# final-project.net
KiCad netlist of a schematic drawn in Altium Designer
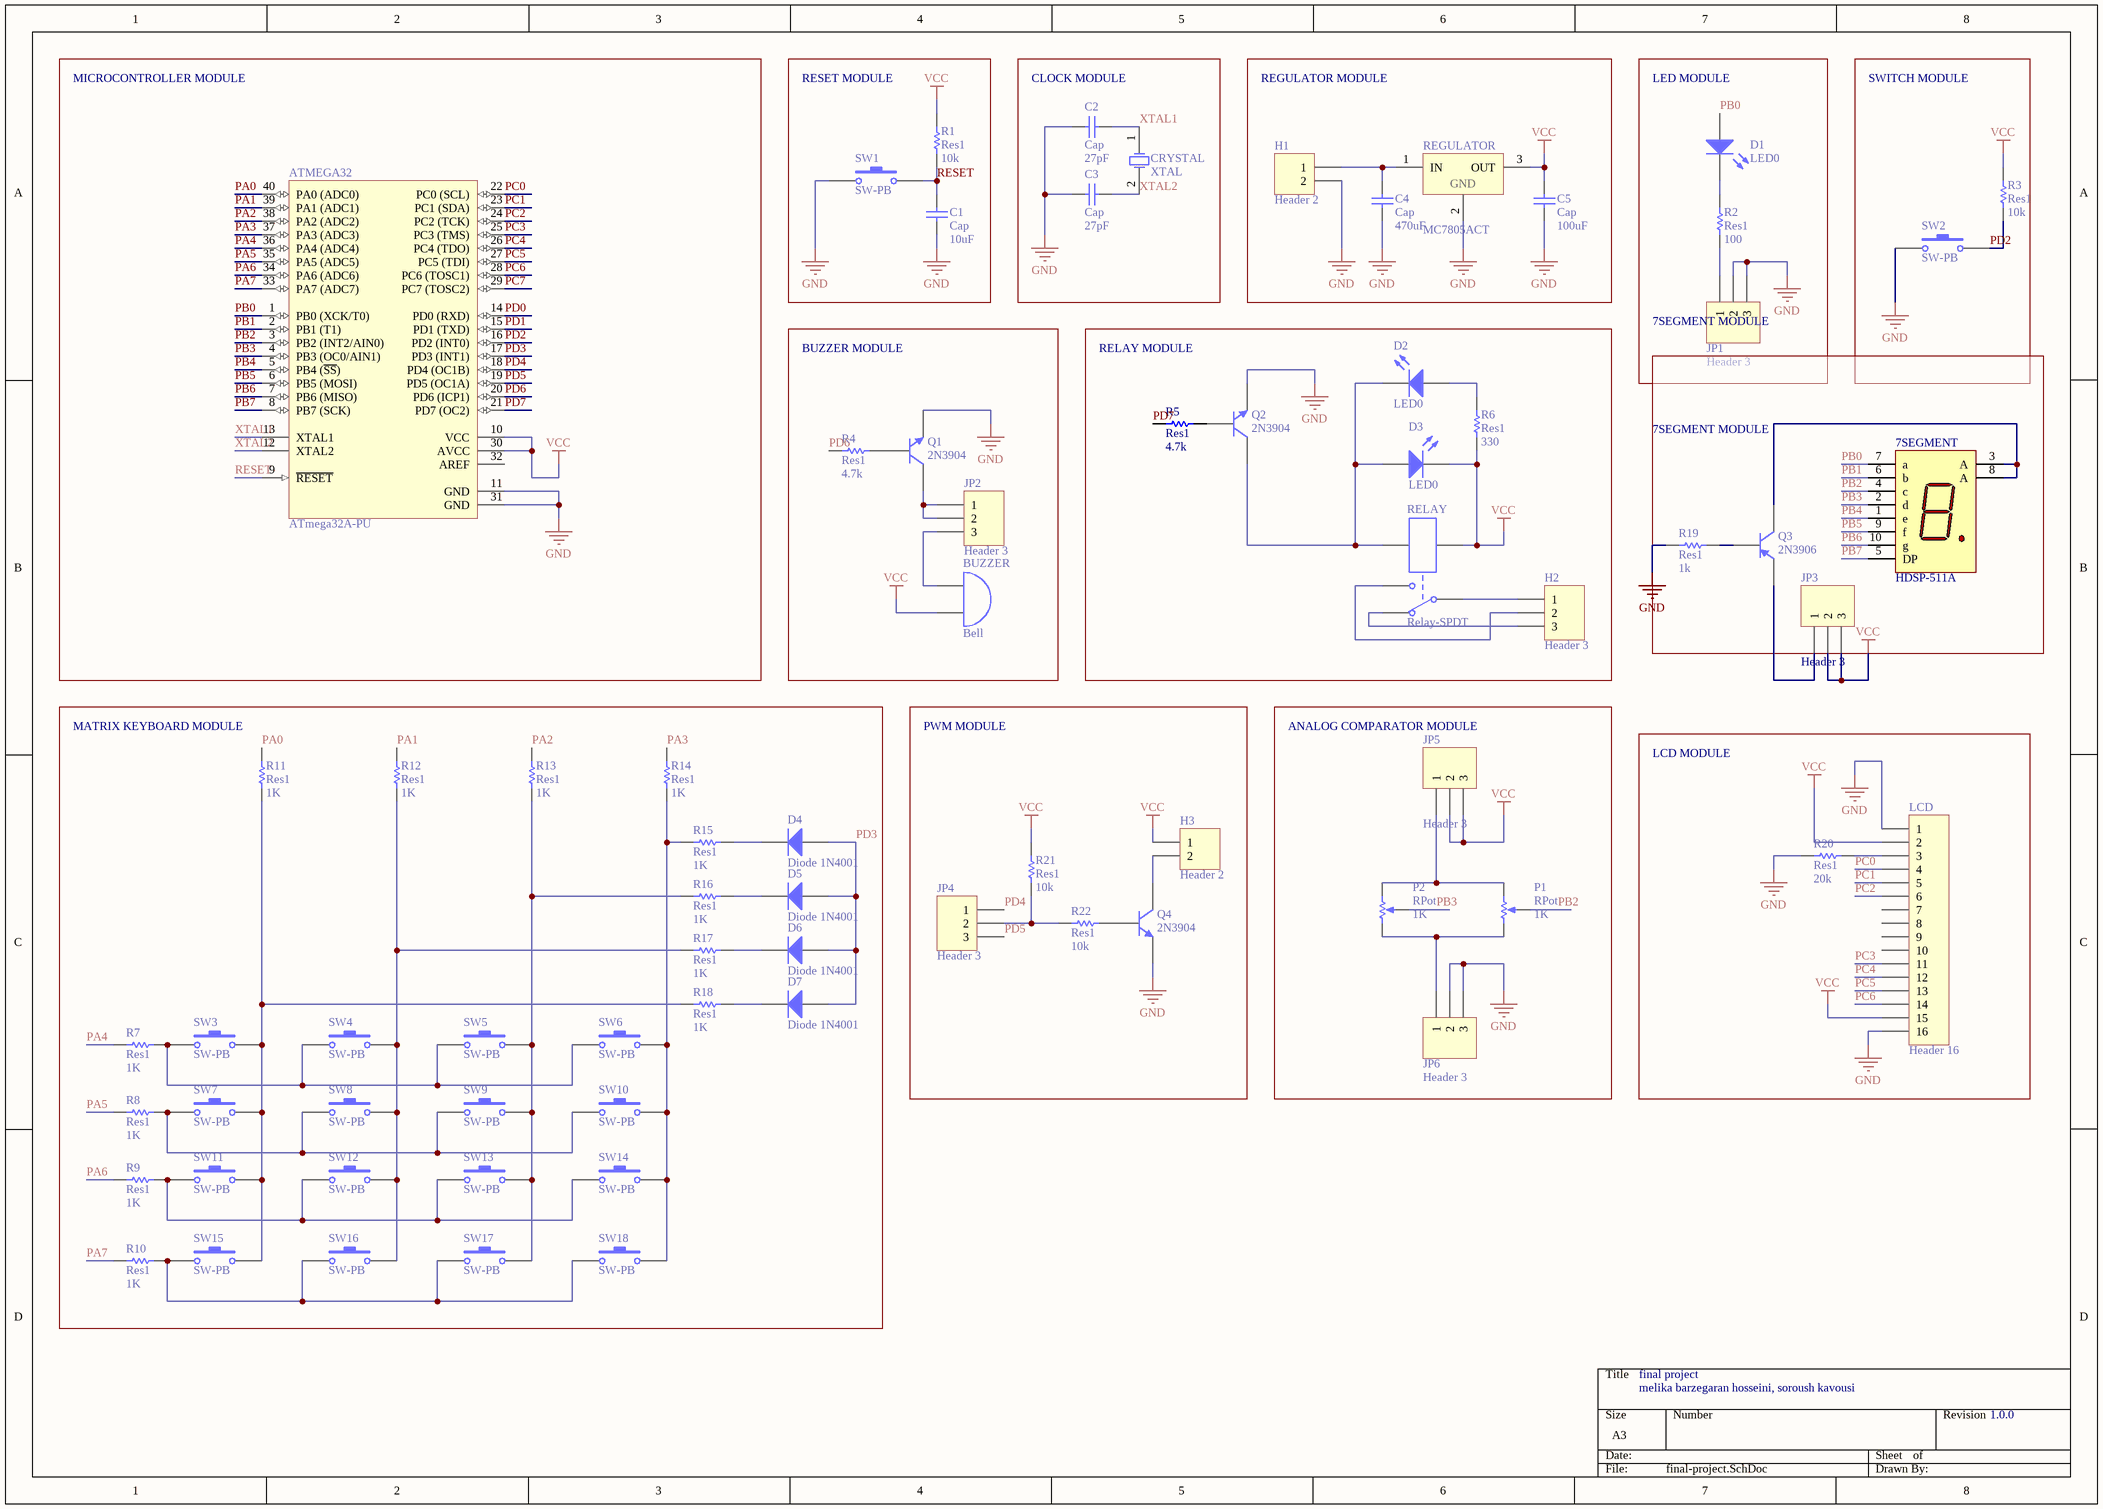
[diagram p0: final-project.SchDoc]

(export (version "E")
  (design (tool "Eeschema 10.0.6"))
  (components
    (comp (ref "7SEGMENT")
      (value "HDSP-511A")
      (footprint "HDSP-51")
      (description "14.22 mm General Purpose AlGaAs Red 7-Segment Display: CA, RH DP")
      (fields (field (name "PUBLISHER") "Altium Limited"))
      (libsource (lib "Agilent LED Display 7-Segment, 1-Digit") (part "HDSP-511A"))
    )
    (comp (ref "ATMEGA32")
      (value "ATmega32A-PU")
      (footprint "40P6")
      (fields (field (name "PUBLISHER") "Altium Limited"))
      (libsource (lib "Atmel Microcontroller 8-Bit megaAVR") (part "ATmega32A-PU"))
    )
    (comp (ref "BUZZER")
      (value "Bell")
      (footprint "PIN2")
      (description "Electrical Bell")
      (fields (field (name "PUBLISHER") "Altium Limited"))
      (libsource (lib "Miscellaneous Devices") (part "Bell"))
    )
    (comp (ref "C1")
      (value "Cap")
      (footprint "RAD-0.3")
      (description "Capacitor")
      (fields (field (name "ALTIUM_VALUE") "10uF") (field (name "PUBLISHER") "Altium Limited"))
      (libsource (lib "Miscellaneous Devices") (part "Cap"))
    )
    (comp (ref "C2")
      (value "Cap")
      (footprint "RAD-0.3")
      (description "Capacitor")
      (fields (field (name "ALTIUM_VALUE") "27pF") (field (name "PUBLISHER") "Altium Limited"))
      (libsource (lib "Miscellaneous Devices") (part "Cap"))
    )
    (comp (ref "C3")
      (value "Cap")
      (footprint "RAD-0.3")
      (description "Capacitor")
      (fields (field (name "ALTIUM_VALUE") "27pF") (field (name "PUBLISHER") "Altium Limited"))
      (libsource (lib "Miscellaneous Devices") (part "Cap"))
    )
    (comp (ref "C4")
      (value "Cap")
      (footprint "RAD-0.3")
      (description "Capacitor")
      (fields (field (name "ALTIUM_VALUE") "470uF") (field (name "PUBLISHER") "Altium Limited"))
      (libsource (lib "Miscellaneous Devices") (part "Cap"))
    )
    (comp (ref "C5")
      (value "Cap")
      (footprint "RAD-0.3")
      (description "Capacitor")
      (fields (field (name "ALTIUM_VALUE") "100uF") (field (name "PUBLISHER") "Altium Limited"))
      (libsource (lib "Miscellaneous Devices") (part "Cap"))
    )
    (comp (ref "CRYSTAL")
      (value "XTAL")
      (footprint "BCY-W2/D3.1")
      (description "Crystal Oscillator")
      (fields (field (name "PUBLISHER") "Altium Limited"))
      (libsource (lib "Miscellaneous Devices") (part "XTAL"))
    )
    (comp (ref "D1")
      (value "LED0")
      (footprint "RB5-10.5")
      (description "Typical INFRARED GaAs LED")
      (fields (field (name "PUBLISHER") "Altium Limited"))
      (libsource (lib "Miscellaneous Devices") (part "LED0"))
    )
    (comp (ref "D2")
      (value "LED0")
      (footprint "RB5-10.5")
      (description "Typical INFRARED GaAs LED")
      (fields (field (name "PUBLISHER") "Altium Limited"))
      (libsource (lib "Miscellaneous Devices") (part "LED0"))
    )
    (comp (ref "D3")
      (value "LED0")
      (footprint "RB5-10.5")
      (description "Typical INFRARED GaAs LED")
      (fields (field (name "PUBLISHER") "Altium Limited"))
      (libsource (lib "Miscellaneous Devices") (part "LED0"))
    )
    (comp (ref "D4")
      (value "Diode 1N4001")
      (footprint "DIO10.46-5.3x2.8")
      (description "1 Amp General Purpose Rectifier")
      (fields (field (name "PUBLISHER") "Altium Limited"))
      (libsource (lib "Miscellaneous Devices") (part "Diode 1N4001"))
    )
    (comp (ref "D5")
      (value "Diode 1N4001")
      (footprint "DIO10.46-5.3x2.8")
      (description "1 Amp General Purpose Rectifier")
      (fields (field (name "PUBLISHER") "Altium Limited"))
      (libsource (lib "Miscellaneous Devices") (part "Diode 1N4001"))
    )
    (comp (ref "D6")
      (value "Diode 1N4001")
      (footprint "DIO10.46-5.3x2.8")
      (description "1 Amp General Purpose Rectifier")
      (fields (field (name "PUBLISHER") "Altium Limited"))
      (libsource (lib "Miscellaneous Devices") (part "Diode 1N4001"))
    )
    (comp (ref "D7")
      (value "Diode 1N4001")
      (footprint "DIO10.46-5.3x2.8")
      (description "1 Amp General Purpose Rectifier")
      (fields (field (name "PUBLISHER") "Altium Limited"))
      (libsource (lib "Miscellaneous Devices") (part "Diode 1N4001"))
    )
    (comp (ref "H1")
      (value "Header 2")
      (footprint "HDR1X2")
      (description "Header, 2-Pin")
      (fields (field (name "PUBLISHER") "Altium Limited"))
      (libsource (lib "Miscellaneous Connectors") (part "Header 2"))
    )
    (comp (ref "H2")
      (value "Header 3")
      (footprint "HDR1X3")
      (description "Header, 3-Pin")
      (fields (field (name "PUBLISHER") "Altium Limited"))
      (libsource (lib "") (part "Header 3_3"))
    )
    (comp (ref "H3")
      (value "Header 2")
      (footprint "HDR1X2")
      (description "Header, 2-Pin")
      (fields (field (name "PUBLISHER") "Altium Limited"))
      (libsource (lib "") (part "Header 2_1"))
    )
    (comp (ref "JP1")
      (value "Header 3")
      (footprint "HDR1X3")
      (description "Header, 3-Pin")
      (fields (field (name "PUBLISHER") "Altium Limited"))
      (libsource (lib "") (part "Header 3_1"))
    )
    (comp (ref "JP2")
      (value "Header 3")
      (footprint "HDR1X3")
      (description "Header, 3-Pin")
      (fields (field (name "PUBLISHER") "Altium Limited"))
      (libsource (lib "") (part "Header 3_3"))
    )
    (comp (ref "JP3")
      (value "Header 3")
      (footprint "HDR1X3")
      (description "Header, 3-Pin")
      (fields (field (name "PUBLISHER") "Altium Limited"))
      (libsource (lib "Miscellaneous Connectors") (part "Header 3"))
    )
    (comp (ref "JP4")
      (value "Header 3")
      (footprint "HDR1X3")
      (description "Header, 3-Pin")
      (fields (field (name "PUBLISHER") "Altium Limited"))
      (libsource (lib "") (part "Header 3_2"))
    )
    (comp (ref "JP5")
      (value "Header 3")
      (footprint "HDR1X3")
      (description "Header, 3-Pin")
      (fields (field (name "PUBLISHER") "Altium Limited"))
      (libsource (lib "Miscellaneous Connectors") (part "Header 3"))
    )
    (comp (ref "JP6")
      (value "Header 3")
      (footprint "HDR1X3")
      (description "Header, 3-Pin")
      (fields (field (name "PUBLISHER") "Altium Limited"))
      (libsource (lib "") (part "Header 3_1"))
    )
    (comp (ref "LCD")
      (value "Header 16")
      (footprint "HDR1X16")
      (description "Header, 16-Pin")
      (fields (field (name "PUBLISHER") "Altium Limited"))
      (libsource (lib "Miscellaneous Connectors") (part "Header 16"))
    )
    (comp (ref "P1")
      (value "RPot")
      (footprint "VR5")
      (description "Potentiometer")
      (fields (field (name "ALTIUM_VALUE") "1K") (field (name "PUBLISHER") "Altium Limited"))
      (libsource (lib "Miscellaneous Devices") (part "RPot"))
    )
    (comp (ref "P2")
      (value "RPot")
      (footprint "VR5")
      (description "Potentiometer")
      (fields (field (name "ALTIUM_VALUE") "1K") (field (name "PUBLISHER") "Altium Limited"))
      (libsource (lib "Miscellaneous Devices") (part "RPot"))
    )
    (comp (ref "Q1")
      (value "2N3904")
      (footprint "HDR1X3")
      (description "NPN General Purpose Amplifier")
      (fields (field (name "PUBLISHER") "Altium Limited"))
      (libsource (lib "Miscellaneous Devices") (part "2N3904"))
    )
    (comp (ref "Q2")
      (value "2N3904")
      (footprint "HDR1X3")
      (description "NPN General Purpose Amplifier")
      (fields (field (name "PUBLISHER") "Altium Limited"))
      (libsource (lib "Miscellaneous Devices") (part "2N3904"))
    )
    (comp (ref "Q3")
      (value "2N3906")
      (footprint "HDR1X3")
      (description "PNP General Purpose Amplifier")
      (fields (field (name "PUBLISHER") "Altium Limited"))
      (libsource (lib "Miscellaneous Devices") (part "2N3906"))
    )
    (comp (ref "Q4")
      (value "2N3904")
      (footprint "HDR1X3")
      (description "NPN General Purpose Amplifier")
      (fields (field (name "PUBLISHER") "Altium Limited"))
      (libsource (lib "Miscellaneous Devices") (part "2N3904"))
    )
    (comp (ref "R1")
      (value "Res1")
      (footprint "AXIAL-0.3")
      (description "Resistor")
      (fields (field (name "ALTIUM_VALUE") "10k") (field (name "PUBLISHER") "Altium Limited"))
      (libsource (lib "Miscellaneous Devices") (part "Res1"))
    )
    (comp (ref "R2")
      (value "Res1")
      (footprint "AXIAL-0.3")
      (description "Resistor")
      (fields (field (name "ALTIUM_VALUE") "100") (field (name "PUBLISHER") "Altium Limited"))
      (libsource (lib "Miscellaneous Devices") (part "Res1"))
    )
    (comp (ref "R3")
      (value "Res1")
      (footprint "AXIAL-0.3")
      (description "Resistor")
      (fields (field (name "ALTIUM_VALUE") "10k") (field (name "PUBLISHER") "Altium Limited"))
      (libsource (lib "Miscellaneous Devices") (part "Res1"))
    )
    (comp (ref "R4")
      (value "Res1")
      (footprint "AXIAL-0.3")
      (description "Resistor")
      (fields (field (name "ALTIUM_VALUE") "4.7k") (field (name "PUBLISHER") "Altium Limited"))
      (libsource (lib "Miscellaneous Devices") (part "Res1"))
    )
    (comp (ref "R5")
      (value "Res1")
      (footprint "AXIAL-0.3")
      (description "Resistor")
      (fields (field (name "ALTIUM_VALUE") "4.7k") (field (name "PUBLISHER") "Altium Limited"))
      (libsource (lib "Miscellaneous Devices") (part "Res1"))
    )
    (comp (ref "R6")
      (value "Res1")
      (footprint "AXIAL-0.3")
      (description "Resistor")
      (fields (field (name "ALTIUM_VALUE") "330") (field (name "PUBLISHER") "Altium Limited"))
      (libsource (lib "Miscellaneous Devices") (part "Res1"))
    )
    (comp (ref "R7")
      (value "Res1")
      (footprint "AXIAL-0.3")
      (description "Resistor")
      (fields (field (name "ALTIUM_VALUE") "1K") (field (name "PUBLISHER") "Altium Limited"))
      (libsource (lib "Miscellaneous Devices") (part "Res1"))
    )
    (comp (ref "R8")
      (value "Res1")
      (footprint "AXIAL-0.3")
      (description "Resistor")
      (fields (field (name "ALTIUM_VALUE") "1K") (field (name "PUBLISHER") "Altium Limited"))
      (libsource (lib "Miscellaneous Devices") (part "Res1"))
    )
    (comp (ref "R9")
      (value "Res1")
      (footprint "AXIAL-0.3")
      (description "Resistor")
      (fields (field (name "ALTIUM_VALUE") "1K") (field (name "PUBLISHER") "Altium Limited"))
      (libsource (lib "Miscellaneous Devices") (part "Res1"))
    )
    (comp (ref "R10")
      (value "Res1")
      (footprint "AXIAL-0.3")
      (description "Resistor")
      (fields (field (name "ALTIUM_VALUE") "1K") (field (name "PUBLISHER") "Altium Limited"))
      (libsource (lib "Miscellaneous Devices") (part "Res1"))
    )
    (comp (ref "R11")
      (value "Res1")
      (footprint "AXIAL-0.3")
      (description "Resistor")
      (fields (field (name "ALTIUM_VALUE") "1K") (field (name "PUBLISHER") "Altium Limited"))
      (libsource (lib "Miscellaneous Devices") (part "Res1"))
    )
    (comp (ref "R12")
      (value "Res1")
      (footprint "AXIAL-0.3")
      (description "Resistor")
      (fields (field (name "ALTIUM_VALUE") "1K") (field (name "PUBLISHER") "Altium Limited"))
      (libsource (lib "Miscellaneous Devices") (part "Res1"))
    )
    (comp (ref "R13")
      (value "Res1")
      (footprint "AXIAL-0.3")
      (description "Resistor")
      (fields (field (name "ALTIUM_VALUE") "1K") (field (name "PUBLISHER") "Altium Limited"))
      (libsource (lib "Miscellaneous Devices") (part "Res1"))
    )
    (comp (ref "R14")
      (value "Res1")
      (footprint "AXIAL-0.3")
      (description "Resistor")
      (fields (field (name "ALTIUM_VALUE") "1K") (field (name "PUBLISHER") "Altium Limited"))
      (libsource (lib "Miscellaneous Devices") (part "Res1"))
    )
    (comp (ref "R15")
      (value "Res1")
      (footprint "AXIAL-0.3")
      (description "Resistor")
      (fields (field (name "ALTIUM_VALUE") "1K") (field (name "PUBLISHER") "Altium Limited"))
      (libsource (lib "Miscellaneous Devices") (part "Res1"))
    )
    (comp (ref "R16")
      (value "Res1")
      (footprint "AXIAL-0.3")
      (description "Resistor")
      (fields (field (name "ALTIUM_VALUE") "1K") (field (name "PUBLISHER") "Altium Limited"))
      (libsource (lib "Miscellaneous Devices") (part "Res1"))
    )
    (comp (ref "R17")
      (value "Res1")
      (footprint "AXIAL-0.3")
      (description "Resistor")
      (fields (field (name "ALTIUM_VALUE") "1K") (field (name "PUBLISHER") "Altium Limited"))
      (libsource (lib "Miscellaneous Devices") (part "Res1"))
    )
    (comp (ref "R18")
      (value "Res1")
      (footprint "AXIAL-0.3")
      (description "Resistor")
      (fields (field (name "ALTIUM_VALUE") "1K") (field (name "PUBLISHER") "Altium Limited"))
      (libsource (lib "Miscellaneous Devices") (part "Res1"))
    )
    (comp (ref "R19")
      (value "Res1")
      (footprint "AXIAL-0.3")
      (description "Resistor")
      (fields (field (name "ALTIUM_VALUE") "1k") (field (name "PUBLISHER") "Altium Limited"))
      (libsource (lib "Miscellaneous Devices") (part "Res1"))
    )
    (comp (ref "R20")
      (value "Res1")
      (footprint "AXIAL-0.3")
      (description "Resistor")
      (fields (field (name "ALTIUM_VALUE") "20k") (field (name "PUBLISHER") "Altium Limited"))
      (libsource (lib "Miscellaneous Devices") (part "Res1"))
    )
    (comp (ref "R21")
      (value "Res1")
      (footprint "AXIAL-0.3")
      (description "Resistor")
      (fields (field (name "ALTIUM_VALUE") "10k") (field (name "PUBLISHER") "Altium Limited"))
      (libsource (lib "Miscellaneous Devices") (part "Res1"))
    )
    (comp (ref "R22")
      (value "Res1")
      (footprint "AXIAL-0.3")
      (description "Resistor")
      (fields (field (name "ALTIUM_VALUE") "10k") (field (name "PUBLISHER") "Altium Limited"))
      (libsource (lib "Miscellaneous Devices") (part "Res1"))
    )
    (comp (ref "REGULATOR")
      (value "MC7805ACT")
      (footprint "221A-04")
      (description "3-Terminal Positive Fixed Voltage Regulator")
      (fields (field (name "PUBLISHER") "Altium Limited"))
      (libsource (lib "Motorola Power Mgt Voltage Regulator") (part "MC7805ACT"))
    )
    (comp (ref "RELAY")
      (value "Relay-SPDT")
      (footprint "DIP-P5/X1.65")
      (description "Single-Pole Dual-Throw Relay")
      (fields (field (name "PUBLISHER") "Altium Limited"))
      (libsource (lib "Miscellaneous Devices") (part "Relay-SPDT"))
    )
    (comp (ref "SW1")
      (value "SW-PB")
      (footprint "SPST-2")
      (description "Switch")
      (fields (field (name "PUBLISHER") "Altium Limited"))
      (libsource (lib "Miscellaneous Devices") (part "SW-PB"))
    )
    (comp (ref "SW2")
      (value "SW-PB")
      (footprint "SPST-2")
      (description "Switch")
      (fields (field (name "PUBLISHER") "Altium Limited"))
      (libsource (lib "Miscellaneous Devices") (part "SW-PB"))
    )
    (comp (ref "SW3")
      (value "SW-PB")
      (footprint "SPST-2")
      (description "Switch")
      (fields (field (name "PUBLISHER") "Altium Limited"))
      (libsource (lib "Miscellaneous Devices") (part "SW-PB"))
    )
    (comp (ref "SW4")
      (value "SW-PB")
      (footprint "SPST-2")
      (description "Switch")
      (fields (field (name "PUBLISHER") "Altium Limited"))
      (libsource (lib "Miscellaneous Devices") (part "SW-PB"))
    )
    (comp (ref "SW5")
      (value "SW-PB")
      (footprint "SPST-2")
      (description "Switch")
      (fields (field (name "PUBLISHER") "Altium Limited"))
      (libsource (lib "Miscellaneous Devices") (part "SW-PB"))
    )
    (comp (ref "SW6")
      (value "SW-PB")
      (footprint "SPST-2")
      (description "Switch")
      (fields (field (name "PUBLISHER") "Altium Limited"))
      (libsource (lib "Miscellaneous Devices") (part "SW-PB"))
    )
    (comp (ref "SW7")
      (value "SW-PB")
      (footprint "SPST-2")
      (description "Switch")
      (fields (field (name "PUBLISHER") "Altium Limited"))
      (libsource (lib "Miscellaneous Devices") (part "SW-PB"))
    )
    (comp (ref "SW8")
      (value "SW-PB")
      (footprint "SPST-2")
      (description "Switch")
      (fields (field (name "PUBLISHER") "Altium Limited"))
      (libsource (lib "Miscellaneous Devices") (part "SW-PB"))
    )
    (comp (ref "SW9")
      (value "SW-PB")
      (footprint "SPST-2")
      (description "Switch")
      (fields (field (name "PUBLISHER") "Altium Limited"))
      (libsource (lib "Miscellaneous Devices") (part "SW-PB"))
    )
    (comp (ref "SW10")
      (value "SW-PB")
      (footprint "SPST-2")
      (description "Switch")
      (fields (field (name "PUBLISHER") "Altium Limited"))
      (libsource (lib "Miscellaneous Devices") (part "SW-PB"))
    )
    (comp (ref "SW11")
      (value "SW-PB")
      (footprint "SPST-2")
      (description "Switch")
      (fields (field (name "PUBLISHER") "Altium Limited"))
      (libsource (lib "Miscellaneous Devices") (part "SW-PB"))
    )
    (comp (ref "SW12")
      (value "SW-PB")
      (footprint "SPST-2")
      (description "Switch")
      (fields (field (name "PUBLISHER") "Altium Limited"))
      (libsource (lib "Miscellaneous Devices") (part "SW-PB"))
    )
    (comp (ref "SW13")
      (value "SW-PB")
      (footprint "SPST-2")
      (description "Switch")
      (fields (field (name "PUBLISHER") "Altium Limited"))
      (libsource (lib "Miscellaneous Devices") (part "SW-PB"))
    )
    (comp (ref "SW14")
      (value "SW-PB")
      (footprint "SPST-2")
      (description "Switch")
      (fields (field (name "PUBLISHER") "Altium Limited"))
      (libsource (lib "Miscellaneous Devices") (part "SW-PB"))
    )
    (comp (ref "SW15")
      (value "SW-PB")
      (footprint "SPST-2")
      (description "Switch")
      (fields (field (name "PUBLISHER") "Altium Limited"))
      (libsource (lib "Miscellaneous Devices") (part "SW-PB"))
    )
    (comp (ref "SW16")
      (value "SW-PB")
      (footprint "SPST-2")
      (description "Switch")
      (fields (field (name "PUBLISHER") "Altium Limited"))
      (libsource (lib "Miscellaneous Devices") (part "SW-PB"))
    )
    (comp (ref "SW17")
      (value "SW-PB")
      (footprint "SPST-2")
      (description "Switch")
      (fields (field (name "PUBLISHER") "Altium Limited"))
      (libsource (lib "Miscellaneous Devices") (part "SW-PB"))
    )
    (comp (ref "SW18")
      (value "SW-PB")
      (footprint "SPST-2")
      (description "Switch")
      (fields (field (name "PUBLISHER") "Altium Limited"))
      (libsource (lib "Miscellaneous Devices") (part "SW-PB"))
    )
  )
  (nets
    (net (code "1") (name "/PA0") (class "Default")
      (node (ref "ATMEGA32") (pin "40") (pinfunction "PA0_(ADC0)_40") (pintype "bidirectional"))
      (node (ref "R11") (pin "2") (pinfunction "2_2") (pintype "passive"))
    )
    (net (code "2") (name "/PA1") (class "Default")
      (node (ref "ATMEGA32") (pin "39") (pinfunction "PA1_(ADC1)_39") (pintype "bidirectional"))
      (node (ref "R12") (pin "2") (pinfunction "2_2") (pintype "passive"))
    )
    (net (code "3") (name "/PA2") (class "Default")
      (node (ref "ATMEGA32") (pin "38") (pinfunction "PA2_(ADC2)_38") (pintype "bidirectional"))
      (node (ref "R13") (pin "2") (pinfunction "2_2") (pintype "passive"))
    )
    (net (code "4") (name "/PA3") (class "Default")
      (node (ref "ATMEGA32") (pin "37") (pinfunction "PA3_(ADC3)_37") (pintype "bidirectional"))
      (node (ref "R14") (pin "2") (pinfunction "2_2") (pintype "passive"))
    )
    (net (code "5") (name "/PA4") (class "Default")
      (node (ref "ATMEGA32") (pin "36") (pinfunction "PA4_(ADC4)_36") (pintype "bidirectional"))
      (node (ref "R7") (pin "1") (pinfunction "1_1") (pintype "passive"))
    )
    (net (code "6") (name "/PA5") (class "Default")
      (node (ref "ATMEGA32") (pin "35") (pinfunction "PA5_(ADC5)_35") (pintype "bidirectional"))
      (node (ref "R8") (pin "1") (pinfunction "1_1") (pintype "passive"))
    )
    (net (code "7") (name "/PA6") (class "Default")
      (node (ref "ATMEGA32") (pin "34") (pinfunction "PA6_(ADC6)_34") (pintype "bidirectional"))
      (node (ref "R9") (pin "1") (pinfunction "1_1") (pintype "passive"))
    )
    (net (code "8") (name "/PA7") (class "Default")
      (node (ref "ATMEGA32") (pin "33") (pinfunction "PA7_(ADC7)_33") (pintype "bidirectional"))
      (node (ref "R10") (pin "1") (pinfunction "1_1") (pintype "passive"))
    )
    (net (code "9") (name "/PB0") (class "Default")
      (node (ref "7SEGMENT") (pin "7") (pinfunction "a_7") (pintype "passive"))
      (node (ref "ATMEGA32") (pin "1") (pinfunction "PB0_(XCK/T0)_1") (pintype "bidirectional"))
      (node (ref "D1") (pin "1") (pinfunction "A_1") (pintype "passive"))
    )
    (net (code "10") (name "/PB1") (class "Default")
      (node (ref "7SEGMENT") (pin "6") (pinfunction "b_6") (pintype "passive"))
      (node (ref "ATMEGA32") (pin "2") (pinfunction "PB1_(T1)_2") (pintype "bidirectional"))
    )
    (net (code "11") (name "/PB2") (class "Default")
      (node (ref "7SEGMENT") (pin "4") (pinfunction "c_4") (pintype "passive"))
      (node (ref "ATMEGA32") (pin "3") (pinfunction "PB2_(INT2/AIN0)_3") (pintype "bidirectional"))
      (node (ref "P1") (pin "3") (pinfunction "TAP_3") (pintype "passive"))
    )
    (net (code "12") (name "/PB3") (class "Default")
      (node (ref "7SEGMENT") (pin "2") (pinfunction "d_2") (pintype "passive"))
      (node (ref "ATMEGA32") (pin "4") (pinfunction "PB3_(OC0/AIN1)_4") (pintype "bidirectional"))
      (node (ref "P2") (pin "3") (pinfunction "TAP_3") (pintype "passive"))
    )
    (net (code "13") (name "/PB4") (class "Default")
      (node (ref "7SEGMENT") (pin "1") (pinfunction "e_1") (pintype "passive"))
      (node (ref "ATMEGA32") (pin "5") (pinfunction "PB4_(~{SS})_5") (pintype "bidirectional"))
    )
    (net (code "14") (name "/PB5") (class "Default")
      (node (ref "7SEGMENT") (pin "9") (pinfunction "f_9") (pintype "passive"))
      (node (ref "ATMEGA32") (pin "6") (pinfunction "PB5_(MOSI)_6") (pintype "bidirectional"))
    )
    (net (code "15") (name "/PB6") (class "Default")
      (node (ref "7SEGMENT") (pin "10") (pinfunction "g_10") (pintype "passive"))
      (node (ref "ATMEGA32") (pin "7") (pinfunction "PB6_(MISO)_7") (pintype "bidirectional"))
    )
    (net (code "16") (name "/PB7") (class "Default")
      (node (ref "7SEGMENT") (pin "5") (pinfunction "DP_5") (pintype "passive"))
      (node (ref "ATMEGA32") (pin "8") (pinfunction "PB7_(SCK)_8") (pintype "bidirectional"))
    )
    (net (code "17") (name "/PC0") (class "Default")
      (node (ref "ATMEGA32") (pin "22") (pinfunction "PC0_(SCL)_22") (pintype "bidirectional"))
      (node (ref "LCD") (pin "4") (pinfunction "4_4") (pintype "passive"))
    )
    (net (code "18") (name "/PC1") (class "Default")
      (node (ref "ATMEGA32") (pin "23") (pinfunction "PC1_(SDA)_23") (pintype "bidirectional"))
      (node (ref "LCD") (pin "5") (pinfunction "5_5") (pintype "passive"))
    )
    (net (code "19") (name "/PC2") (class "Default")
      (node (ref "ATMEGA32") (pin "24") (pinfunction "PC2_(TCK)_24") (pintype "bidirectional"))
      (node (ref "LCD") (pin "6") (pinfunction "6_6") (pintype "passive"))
    )
    (net (code "20") (name "/PC3") (class "Default")
      (node (ref "ATMEGA32") (pin "25") (pinfunction "PC3_(TMS)_25") (pintype "bidirectional"))
      (node (ref "LCD") (pin "11") (pinfunction "11_11") (pintype "passive"))
    )
    (net (code "21") (name "/PC4") (class "Default")
      (node (ref "ATMEGA32") (pin "26") (pinfunction "PC4_(TDO)_26") (pintype "bidirectional"))
      (node (ref "LCD") (pin "12") (pinfunction "12_12") (pintype "passive"))
    )
    (net (code "22") (name "/PC5") (class "Default")
      (node (ref "ATMEGA32") (pin "27") (pinfunction "PC5_(TDI)_27") (pintype "bidirectional"))
      (node (ref "LCD") (pin "13") (pinfunction "13_13") (pintype "passive"))
    )
    (net (code "23") (name "/PC6") (class "Default")
      (node (ref "ATMEGA32") (pin "28") (pinfunction "PC6_(TOSC1)_28") (pintype "bidirectional"))
      (node (ref "LCD") (pin "14") (pinfunction "14_14") (pintype "passive"))
    )
    (net (code "24") (name "/PC7") (class "Default")
      (node (ref "ATMEGA32") (pin "29") (pinfunction "PC7_(TOSC2)_29") (pintype "bidirectional"))
    )
    (net (code "25") (name "/PD0") (class "Default")
      (node (ref "ATMEGA32") (pin "14") (pinfunction "PD0_(RXD)_14") (pintype "bidirectional"))
    )
    (net (code "26") (name "/PD1") (class "Default")
      (node (ref "ATMEGA32") (pin "15") (pinfunction "PD1_(TXD)_15") (pintype "bidirectional"))
    )
    (net (code "27") (name "/PD2") (class "Default")
      (node (ref "ATMEGA32") (pin "16") (pinfunction "PD2_(INT0)_16") (pintype "bidirectional"))
      (node (ref "R3") (pin "1") (pinfunction "1_1") (pintype "passive"))
      (node (ref "SW2") (pin "2") (pinfunction "2_2") (pintype "passive"))
    )
    (net (code "28") (name "/PD3") (class "Default")
      (node (ref "ATMEGA32") (pin "17") (pinfunction "PD3_(INT1)_17") (pintype "bidirectional"))
      (node (ref "D4") (pin "1") (pinfunction "A_1") (pintype "passive"))
      (node (ref "D5") (pin "1") (pinfunction "A_1") (pintype "passive"))
      (node (ref "D6") (pin "1") (pinfunction "A_1") (pintype "passive"))
      (node (ref "D7") (pin "1") (pinfunction "A_1") (pintype "passive"))
    )
    (net (code "29") (name "/PD4") (class "Default")
      (node (ref "ATMEGA32") (pin "18") (pinfunction "PD4_(OC1B)_18") (pintype "bidirectional"))
      (node (ref "JP4") (pin "1") (pinfunction "1_1") (pintype "passive"))
    )
    (net (code "30") (name "/PD5") (class "Default")
      (node (ref "ATMEGA32") (pin "19") (pinfunction "PD5_(OC1A)_19") (pintype "bidirectional"))
      (node (ref "JP4") (pin "3") (pinfunction "3_3") (pintype "passive"))
    )
    (net (code "31") (name "/PD6") (class "Default")
      (node (ref "ATMEGA32") (pin "20") (pinfunction "PD6_(ICP1)_20") (pintype "bidirectional"))
      (node (ref "R4") (pin "1") (pinfunction "1_1") (pintype "passive"))
    )
    (net (code "32") (name "/PD7") (class "Default")
      (node (ref "ATMEGA32") (pin "21") (pinfunction "PD7_(OC2)_21") (pintype "bidirectional"))
      (node (ref "R5") (pin "1") (pinfunction "1_1") (pintype "passive"))
    )
    (net (code "33") (name "/RESET") (class "Default")
      (node (ref "ATMEGA32") (pin "9") (pinfunction "~{RESET}_9") (pintype "input"))
      (node (ref "C1") (pin "2") (pinfunction "2_2") (pintype "passive"))
      (node (ref "R1") (pin "1") (pinfunction "1_1") (pintype "passive"))
      (node (ref "SW1") (pin "2") (pinfunction "2_2") (pintype "passive"))
    )
    (net (code "34") (name "/XTAL1") (class "Default")
      (node (ref "ATMEGA32") (pin "13") (pinfunction "XTAL1_13") (pintype "passive"))
      (node (ref "C2") (pin "2") (pinfunction "2_2") (pintype "passive"))
      (node (ref "CRYSTAL") (pin "1") (pinfunction "OSC1_1") (pintype "passive"))
    )
    (net (code "35") (name "/XTAL2") (class "Default")
      (node (ref "ATMEGA32") (pin "12") (pinfunction "XTAL2_12") (pintype "passive"))
      (node (ref "C3") (pin "2") (pinfunction "2_2") (pintype "passive"))
      (node (ref "CRYSTAL") (pin "2") (pinfunction "OSC2_2") (pintype "passive"))
    )
    (net (code "36") (name "GND") (class "Default")
      (node (ref "ATMEGA32") (pin "11") (pinfunction "GND_11") (pintype "power_in"))
      (node (ref "ATMEGA32") (pin "31") (pinfunction "GND_31") (pintype "power_in"))
      (node (ref "C1") (pin "1") (pinfunction "1_1") (pintype "passive"))
      (node (ref "C2") (pin "1") (pinfunction "1_1") (pintype "passive"))
      (node (ref "C3") (pin "1") (pinfunction "1_1") (pintype "passive"))
      (node (ref "C4") (pin "1") (pinfunction "1_1") (pintype "passive"))
      (node (ref "C5") (pin "1") (pinfunction "1_1") (pintype "passive"))
      (node (ref "H1") (pin "2") (pinfunction "2_2") (pintype "passive"))
      (node (ref "JP1") (pin "2") (pinfunction "2_2") (pintype "passive"))
      (node (ref "JP1") (pin "3") (pinfunction "3_3") (pintype "passive"))
      (node (ref "JP6") (pin "2") (pinfunction "2_2") (pintype "passive"))
      (node (ref "JP6") (pin "3") (pinfunction "3_3") (pintype "passive"))
      (node (ref "LCD") (pin "1") (pinfunction "1_1") (pintype "passive"))
      (node (ref "LCD") (pin "16") (pinfunction "16_16") (pintype "passive"))
      (node (ref "Q1") (pin "1") (pinfunction "E_1") (pintype "passive"))
      (node (ref "Q2") (pin "1") (pinfunction "E_1") (pintype "passive"))
      (node (ref "Q4") (pin "1") (pinfunction "E_1") (pintype "passive"))
      (node (ref "R19") (pin "1") (pinfunction "1_1") (pintype "passive"))
      (node (ref "R20") (pin "1") (pinfunction "1_1") (pintype "passive"))
      (node (ref "REGULATOR") (pin "2") (pinfunction "GND_2") (pintype "power_in"))
      (node (ref "SW1") (pin "1") (pinfunction "1_1") (pintype "passive"))
      (node (ref "SW2") (pin "1") (pinfunction "1_1") (pintype "passive"))
    )
    (net (code "37") (name "Net-(BUZZER-A)") (class "Default")
      (node (ref "BUZZER") (pin "1") (pinfunction "A_1") (pintype "passive"))
      (node (ref "JP2") (pin "3") (pinfunction "3_3") (pintype "passive"))
    )
    (net (code "38") (name "Net-(D1-K)") (class "Default")
      (node (ref "D1") (pin "2") (pinfunction "K_2") (pintype "passive"))
      (node (ref "R2") (pin "2") (pinfunction "2_2") (pintype "passive"))
    )
    (net (code "39") (name "Net-(D2-A)") (class "Default")
      (node (ref "D2") (pin "1") (pinfunction "A_1") (pintype "passive"))
      (node (ref "R6") (pin "2") (pinfunction "2_2") (pintype "passive"))
    )
    (net (code "40") (name "Net-(D2-K)") (class "Default")
      (node (ref "D2") (pin "2") (pinfunction "K_2") (pintype "passive"))
      (node (ref "D3") (pin "1") (pinfunction "A_1") (pintype "passive"))
      (node (ref "Q2") (pin "3") (pinfunction "C_3") (pintype "passive"))
      (node (ref "RELAY") (pin "5") (pinfunction "5_5") (pintype "passive"))
    )
    (net (code "41") (name "Net-(D4-K)") (class "Default")
      (node (ref "D4") (pin "2") (pinfunction "K_2") (pintype "passive"))
      (node (ref "R15") (pin "2") (pinfunction "2_2") (pintype "passive"))
    )
    (net (code "42") (name "Net-(D5-K)") (class "Default")
      (node (ref "D5") (pin "2") (pinfunction "K_2") (pintype "passive"))
      (node (ref "R16") (pin "2") (pinfunction "2_2") (pintype "passive"))
    )
    (net (code "43") (name "Net-(D6-K)") (class "Default")
      (node (ref "D6") (pin "2") (pinfunction "K_2") (pintype "passive"))
      (node (ref "R17") (pin "2") (pinfunction "2_2") (pintype "passive"))
    )
    (net (code "44") (name "Net-(D7-K)") (class "Default")
      (node (ref "D7") (pin "2") (pinfunction "K_2") (pintype "passive"))
      (node (ref "R18") (pin "2") (pinfunction "2_2") (pintype "passive"))
    )
    (net (code "45") (name "Net-(H2-Pad1)") (class "Default")
      (node (ref "H2") (pin "1") (pinfunction "1_1") (pintype "passive"))
      (node (ref "RELAY") (pin "1") (pinfunction "1_1") (pintype "passive"))
    )
    (net (code "46") (name "Net-(H2-Pad2)") (class "Default")
      (node (ref "H2") (pin "2") (pinfunction "2_2") (pintype "passive"))
      (node (ref "RELAY") (pin "3") (pinfunction "3_3") (pintype "passive"))
    )
    (net (code "47") (name "Net-(H2-Pad3)") (class "Default")
      (node (ref "H2") (pin "3") (pinfunction "3_3") (pintype "passive"))
      (node (ref "RELAY") (pin "2") (pinfunction "2_2") (pintype "passive"))
    )
    (net (code "48") (name "Net-(JP1-Pad1)") (class "Default")
      (node (ref "JP1") (pin "1") (pinfunction "1_1") (pintype "passive"))
      (node (ref "R2") (pin "1") (pinfunction "1_1") (pintype "passive"))
    )
    (net (code "49") (name "Net-(JP4-Pad2)") (class "Default")
      (node (ref "JP4") (pin "2") (pinfunction "2_2") (pintype "passive"))
      (node (ref "R21") (pin "1") (pinfunction "1_1") (pintype "passive"))
      (node (ref "R22") (pin "1") (pinfunction "1_1") (pintype "passive"))
    )
    (net (code "50") (name "Net-(LCD-Pad3)") (class "Default")
      (node (ref "LCD") (pin "3") (pinfunction "3_3") (pintype "passive"))
      (node (ref "R20") (pin "2") (pinfunction "2_2") (pintype "passive"))
    )
    (net (code "51") (name "Net-(P1-BOT)") (class "Default")
      (node (ref "JP5") (pin "1") (pinfunction "1_1") (pintype "passive"))
      (node (ref "P1") (pin "2") (pinfunction "BOT_2") (pintype "passive"))
      (node (ref "P2") (pin "2") (pinfunction "BOT_2") (pintype "passive"))
    )
    (net (code "52") (name "Net-(P1-TOP)") (class "Default")
      (node (ref "JP6") (pin "1") (pinfunction "1_1") (pintype "passive"))
      (node (ref "P1") (pin "1") (pinfunction "TOP_1") (pintype "passive"))
      (node (ref "P2") (pin "1") (pinfunction "TOP_1") (pintype "passive"))
    )
    (net (code "53") (name "Net-(Q1-B)") (class "Default")
      (node (ref "Q1") (pin "2") (pinfunction "B_2") (pintype "passive"))
      (node (ref "R4") (pin "2") (pinfunction "2_2") (pintype "passive"))
    )
    (net (code "54") (name "Net-(Q1-C)") (class "Default")
      (node (ref "JP2") (pin "1") (pinfunction "1_1") (pintype "passive"))
      (node (ref "JP2") (pin "2") (pinfunction "2_2") (pintype "passive"))
      (node (ref "Q1") (pin "3") (pinfunction "C_3") (pintype "passive"))
    )
    (net (code "55") (name "Net-(Q2-B)") (class "Default")
      (node (ref "Q2") (pin "2") (pinfunction "B_2") (pintype "passive"))
      (node (ref "R5") (pin "2") (pinfunction "2_2") (pintype "passive"))
    )
    (net (code "56") (name "Net-(Q3-B)") (class "Default")
      (node (ref "Q3") (pin "2") (pinfunction "B_2") (pintype "passive"))
      (node (ref "R19") (pin "2") (pinfunction "2_2") (pintype "passive"))
    )
    (net (code "57") (name "Net-(Q3-C)") (class "Default")
      (node (ref "7SEGMENT") (pin "3") (pinfunction "A_3") (pintype "passive"))
      (node (ref "7SEGMENT") (pin "8") (pinfunction "A_8") (pintype "passive"))
      (node (ref "Q3") (pin "3") (pinfunction "C_3") (pintype "passive"))
    )
    (net (code "58") (name "Net-(Q3-E)") (class "Default")
      (node (ref "JP3") (pin "1") (pinfunction "1_1") (pintype "passive"))
      (node (ref "Q3") (pin "1") (pinfunction "E_1") (pintype "passive"))
    )
    (net (code "59") (name "Net-(Q4-B)") (class "Default")
      (node (ref "Q4") (pin "2") (pinfunction "B_2") (pintype "passive"))
      (node (ref "R22") (pin "2") (pinfunction "2_2") (pintype "passive"))
    )
    (net (code "60") (name "Net-(Q4-C)") (class "Default")
      (node (ref "H3") (pin "2") (pinfunction "2_2") (pintype "passive"))
      (node (ref "Q4") (pin "3") (pinfunction "C_3") (pintype "passive"))
    )
    (net (code "61") (name "Net-(R7-Pad2)") (class "Default")
      (node (ref "R7") (pin "2") (pinfunction "2_2") (pintype "passive"))
      (node (ref "SW3") (pin "1") (pinfunction "1_1") (pintype "passive"))
      (node (ref "SW4") (pin "1") (pinfunction "1_1") (pintype "passive"))
      (node (ref "SW5") (pin "1") (pinfunction "1_1") (pintype "passive"))
      (node (ref "SW6") (pin "1") (pinfunction "1_1") (pintype "passive"))
    )
    (net (code "62") (name "Net-(R8-Pad2)") (class "Default")
      (node (ref "R8") (pin "2") (pinfunction "2_2") (pintype "passive"))
      (node (ref "SW10") (pin "1") (pinfunction "1_1") (pintype "passive"))
      (node (ref "SW7") (pin "1") (pinfunction "1_1") (pintype "passive"))
      (node (ref "SW8") (pin "1") (pinfunction "1_1") (pintype "passive"))
      (node (ref "SW9") (pin "1") (pinfunction "1_1") (pintype "passive"))
    )
    (net (code "63") (name "Net-(R9-Pad2)") (class "Default")
      (node (ref "R9") (pin "2") (pinfunction "2_2") (pintype "passive"))
      (node (ref "SW11") (pin "1") (pinfunction "1_1") (pintype "passive"))
      (node (ref "SW12") (pin "1") (pinfunction "1_1") (pintype "passive"))
      (node (ref "SW13") (pin "1") (pinfunction "1_1") (pintype "passive"))
      (node (ref "SW14") (pin "1") (pinfunction "1_1") (pintype "passive"))
    )
    (net (code "64") (name "Net-(R10-Pad2)") (class "Default")
      (node (ref "R10") (pin "2") (pinfunction "2_2") (pintype "passive"))
      (node (ref "SW15") (pin "1") (pinfunction "1_1") (pintype "passive"))
      (node (ref "SW16") (pin "1") (pinfunction "1_1") (pintype "passive"))
      (node (ref "SW17") (pin "1") (pinfunction "1_1") (pintype "passive"))
      (node (ref "SW18") (pin "1") (pinfunction "1_1") (pintype "passive"))
    )
    (net (code "65") (name "Net-(R11-Pad1)") (class "Default")
      (node (ref "R11") (pin "1") (pinfunction "1_1") (pintype "passive"))
      (node (ref "R18") (pin "1") (pinfunction "1_1") (pintype "passive"))
      (node (ref "SW11") (pin "2") (pinfunction "2_2") (pintype "passive"))
      (node (ref "SW15") (pin "2") (pinfunction "2_2") (pintype "passive"))
      (node (ref "SW3") (pin "2") (pinfunction "2_2") (pintype "passive"))
      (node (ref "SW7") (pin "2") (pinfunction "2_2") (pintype "passive"))
    )
    (net (code "66") (name "Net-(R12-Pad1)") (class "Default")
      (node (ref "R12") (pin "1") (pinfunction "1_1") (pintype "passive"))
      (node (ref "R17") (pin "1") (pinfunction "1_1") (pintype "passive"))
      (node (ref "SW12") (pin "2") (pinfunction "2_2") (pintype "passive"))
      (node (ref "SW16") (pin "2") (pinfunction "2_2") (pintype "passive"))
      (node (ref "SW4") (pin "2") (pinfunction "2_2") (pintype "passive"))
      (node (ref "SW8") (pin "2") (pinfunction "2_2") (pintype "passive"))
    )
    (net (code "67") (name "Net-(R13-Pad1)") (class "Default")
      (node (ref "R13") (pin "1") (pinfunction "1_1") (pintype "passive"))
      (node (ref "R16") (pin "1") (pinfunction "1_1") (pintype "passive"))
      (node (ref "SW13") (pin "2") (pinfunction "2_2") (pintype "passive"))
      (node (ref "SW17") (pin "2") (pinfunction "2_2") (pintype "passive"))
      (node (ref "SW5") (pin "2") (pinfunction "2_2") (pintype "passive"))
      (node (ref "SW9") (pin "2") (pinfunction "2_2") (pintype "passive"))
    )
    (net (code "68") (name "Net-(R14-Pad1)") (class "Default")
      (node (ref "R14") (pin "1") (pinfunction "1_1") (pintype "passive"))
      (node (ref "R15") (pin "1") (pinfunction "1_1") (pintype "passive"))
      (node (ref "SW10") (pin "2") (pinfunction "2_2") (pintype "passive"))
      (node (ref "SW14") (pin "2") (pinfunction "2_2") (pintype "passive"))
      (node (ref "SW18") (pin "2") (pinfunction "2_2") (pintype "passive"))
      (node (ref "SW6") (pin "2") (pinfunction "2_2") (pintype "passive"))
    )
    (net (code "69") (name "Net-(REGULATOR-IN)") (class "Default")
      (node (ref "C4") (pin "2") (pinfunction "2_2") (pintype "passive"))
      (node (ref "H1") (pin "1") (pinfunction "1_1") (pintype "passive"))
      (node (ref "REGULATOR") (pin "1") (pinfunction "IN_1") (pintype "power_in"))
    )
    (net (code "70") (name "VCC") (class "Default")
      (node (ref "ATMEGA32") (pin "10") (pinfunction "VCC_10") (pintype "power_in"))
      (node (ref "ATMEGA32") (pin "30") (pinfunction "AVCC_30") (pintype "power_in"))
      (node (ref "BUZZER") (pin "2") (pinfunction "B_2") (pintype "passive"))
      (node (ref "C5") (pin "2") (pinfunction "2_2") (pintype "passive"))
      (node (ref "D3") (pin "2") (pinfunction "K_2") (pintype "passive"))
      (node (ref "H3") (pin "1") (pinfunction "1_1") (pintype "passive"))
      (node (ref "JP3") (pin "2") (pinfunction "2_2") (pintype "passive"))
      (node (ref "JP3") (pin "3") (pinfunction "3_3") (pintype "passive"))
      (node (ref "JP5") (pin "2") (pinfunction "2_2") (pintype "passive"))
      (node (ref "JP5") (pin "3") (pinfunction "3_3") (pintype "passive"))
      (node (ref "LCD") (pin "15") (pinfunction "15_15") (pintype "passive"))
      (node (ref "LCD") (pin "2") (pinfunction "2_2") (pintype "passive"))
      (node (ref "R1") (pin "2") (pinfunction "2_2") (pintype "passive"))
      (node (ref "R21") (pin "2") (pinfunction "2_2") (pintype "passive"))
      (node (ref "R3") (pin "2") (pinfunction "2_2") (pintype "passive"))
      (node (ref "R6") (pin "1") (pinfunction "1_1") (pintype "passive"))
      (node (ref "REGULATOR") (pin "3") (pinfunction "OUT_3") (pintype "power_in"))
      (node (ref "RELAY") (pin "4") (pinfunction "4_4") (pintype "passive"))
    )
    (net (code "71") (name "unconnected-(ATMEGA32-AREF-Pad32)") (class "Default")
      (node (ref "ATMEGA32") (pin "32") (pinfunction "AREF_32") (pintype "power_in"))
    )
    (net (code "72") (name "unconnected-(LCD-Pad7)") (class "Default")
      (node (ref "LCD") (pin "7") (pinfunction "7_7") (pintype "passive"))
    )
    (net (code "73") (name "unconnected-(LCD-Pad8)") (class "Default")
      (node (ref "LCD") (pin "8") (pinfunction "8_8") (pintype "passive"))
    )
    (net (code "74") (name "unconnected-(LCD-Pad9)") (class "Default")
      (node (ref "LCD") (pin "9") (pinfunction "9_9") (pintype "passive"))
    )
    (net (code "75") (name "unconnected-(LCD-Pad10)") (class "Default")
      (node (ref "LCD") (pin "10") (pinfunction "10_10") (pintype "passive"))
    )
  )
)
